# twitter-magnet.net
KiCad netlist of a schematic drawn in EAGLE
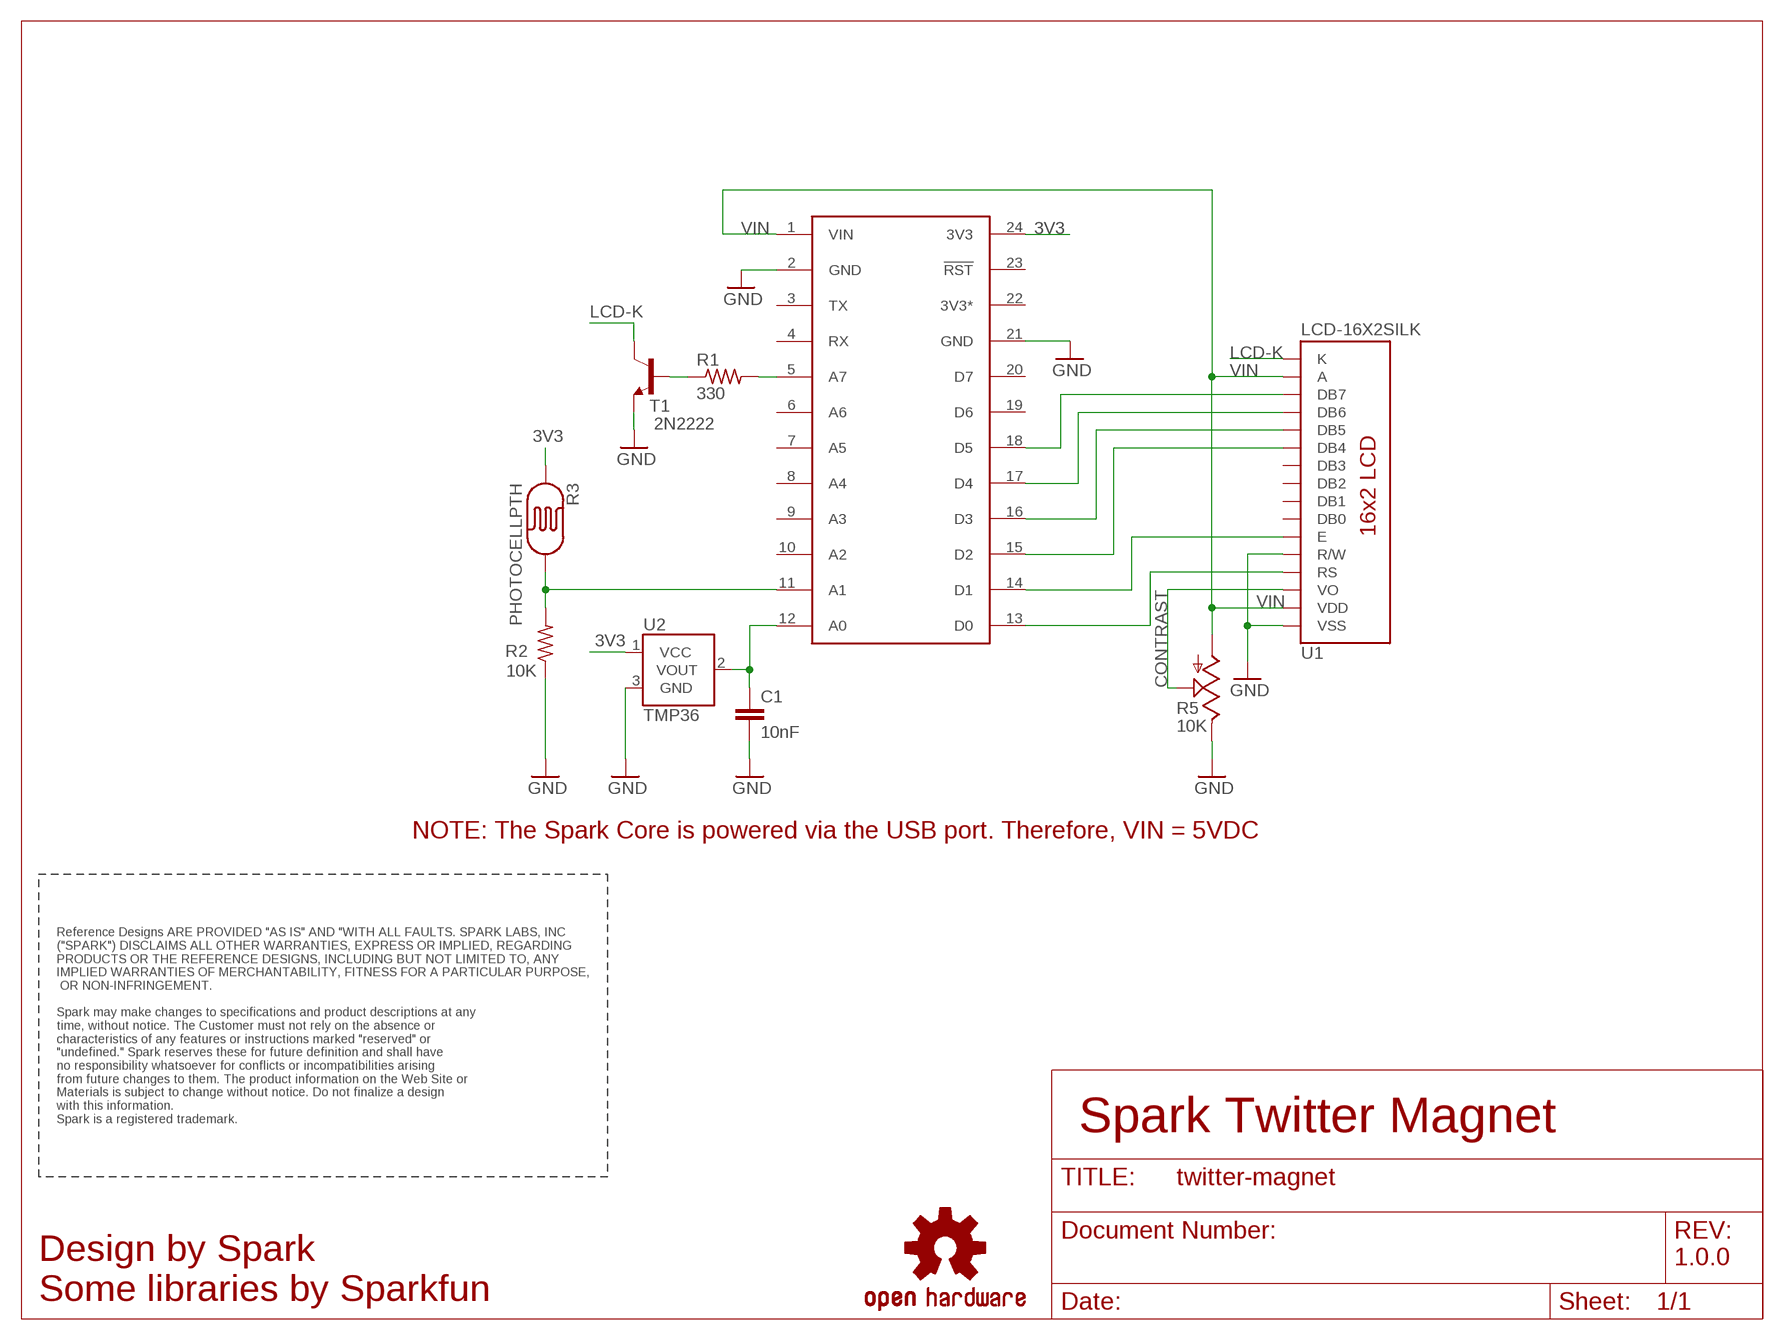
[diagram p0: schematic, sheet 1]

(export (version "E")
  (design (tool "Eeschema 10.0.6"))
  (components
    (comp (ref "C1")
      (value "10nF")
      (footprint "eagle-import:CAP-PTH-SMALLEZ")
      (libsource (lib "eagle-import") (part "CAPEZ"))
    )
    (comp (ref "LOGO1")
      (value "OSHW-LOGOM")
      (footprint "eagle-import:OSHW-LOGO-M")
      (libsource (lib "eagle-import") (part "OSHW-LOGOM"))
    )
    (comp (ref "R1")
      (value "330")
      (footprint "eagle-import:0207_10")
      (libsource (lib "eagle-import") (part "R-US_0207/10"))
    )
    (comp (ref "R2")
      (value "10K")
      (footprint "eagle-import:0207_10")
      (libsource (lib "eagle-import") (part "R-US_0207/10"))
    )
    (comp (ref "R3")
      (value "PHOTOCELLPTH")
      (footprint "eagle-import:PHOTOCELL")
      (libsource (lib "eagle-import") (part "PHOTOCELLPTH"))
    )
    (comp (ref "R5")
      (value "10K")
      (footprint "eagle-import:B25X")
      (libsource (lib "eagle-import") (part "TRIM_US-B25X"))
    )
    (comp (ref "T1")
      (value "2N2222")
      (footprint "eagle-import:TO92-EBC")
      (libsource (lib "eagle-import") (part "-NPN-TO92-EBC"))
    )
    (comp (ref "U$1")
      (value "SPARK_CORECORE")
      (footprint "eagle-import:SPARK_CORE")
      (libsource (lib "eagle-import") (part "SPARK_CORECORE"))
    )
    (comp (ref "U1")
      (value "LCD-16X2SILK")
      (footprint "eagle-import:LCD-16X2")
      (libsource (lib "eagle-import") (part "LCD-16X2SILK"))
    )
    (comp (ref "U2")
      (value "TMP36")
      (footprint "eagle-import:TO-92-KIT")
      (libsource (lib "eagle-import") (part "TMP36TO-92-KIT"))
    )
  )
  (nets
    (net (code "1") (name "/3V3") (class "Default")
      (node (ref "R3") (pin "1") (pinfunction "P$1_1") (pintype "bidirectional"))
      (node (ref "U$1") (pin "24") (pinfunction "3V3_24") (pintype "power_in"))
      (node (ref "U2") (pin "1") (pinfunction "VCC_1") (pintype "bidirectional"))
    )
    (net (code "2") (name "/3V3*") (class "Default")
      (node (ref "U$1") (pin "22") (pinfunction "3V3*_22") (pintype "power_in"))
    )
    (net (code "3") (name "/CONTRAST") (class "Default")
      (node (ref "R5") (pin "S") (pinfunction "S_S") (pintype "passive"))
      (node (ref "U1") (pin "3") (pinfunction "VO_3") (pintype "bidirectional"))
    )
    (net (code "4") (name "/LCD-K") (class "Default")
      (node (ref "T1") (pin "C") (pinfunction "C_C") (pintype "passive"))
      (node (ref "U1") (pin "16") (pinfunction "K_16") (pintype "power_in"))
    )
    (net (code "5") (name "/VIN") (class "Default")
      (node (ref "R5") (pin "A") (pinfunction "A_A") (pintype "passive"))
      (node (ref "U$1") (pin "1") (pinfunction "VIN_1") (pintype "power_in"))
      (node (ref "U1") (pin "15") (pinfunction "A_15") (pintype "power_in"))
      (node (ref "U1") (pin "2") (pinfunction "VDD_2") (pintype "power_in"))
    )
    (net (code "6") (name "GND") (class "Default")
      (node (ref "C1") (pin "2") (pinfunction "2_2") (pintype "passive"))
      (node (ref "R2") (pin "1") (pinfunction "1_1") (pintype "passive"))
      (node (ref "R5") (pin "E") (pinfunction "E_E") (pintype "passive"))
      (node (ref "T1") (pin "E") (pinfunction "E_E") (pintype "passive"))
      (node (ref "U$1") (pin "2") (pinfunction "GND_2") (pintype "power_in"))
      (node (ref "U$1") (pin "21") (pinfunction "GND_21") (pintype "power_in"))
      (node (ref "U1") (pin "1") (pinfunction "VSS_1") (pintype "power_in"))
      (node (ref "U1") (pin "5") (pinfunction "R/W_5") (pintype "input"))
      (node (ref "U2") (pin "3") (pinfunction "GND_3") (pintype "bidirectional"))
    )
    (net (code "7") (name "Net-(R1-Pad1)") (class "Default")
      (node (ref "R1") (pin "1") (pinfunction "1_1") (pintype "passive"))
      (node (ref "T1") (pin "B") (pinfunction "B_B") (pintype "passive"))
    )
    (net (code "8") (name "Net-(R3-P$2)") (class "Default")
      (node (ref "R2") (pin "2") (pinfunction "2_2") (pintype "passive"))
      (node (ref "R3") (pin "2") (pinfunction "P$2_2") (pintype "bidirectional"))
      (node (ref "U$1") (pin "11") (pinfunction "A1_11") (pintype "bidirectional"))
    )
    (net (code "9") (name "Net-(U$1-A0)") (class "Default")
      (node (ref "C1") (pin "1") (pinfunction "1_1") (pintype "passive"))
      (node (ref "U$1") (pin "12") (pinfunction "A0_12") (pintype "bidirectional"))
      (node (ref "U2") (pin "2") (pinfunction "VOUT_2") (pintype "bidirectional"))
    )
    (net (code "10") (name "Net-(U$1-A7)") (class "Default")
      (node (ref "R1") (pin "2") (pinfunction "2_2") (pintype "passive"))
      (node (ref "U$1") (pin "5") (pinfunction "A7_5") (pintype "bidirectional"))
    )
    (net (code "11") (name "Net-(U$1-D0)") (class "Default")
      (node (ref "U$1") (pin "13") (pinfunction "D0_13") (pintype "bidirectional"))
      (node (ref "U1") (pin "4") (pinfunction "RS_4") (pintype "input"))
    )
    (net (code "12") (name "Net-(U$1-D1)") (class "Default")
      (node (ref "U$1") (pin "14") (pinfunction "D1_14") (pintype "bidirectional"))
      (node (ref "U1") (pin "6") (pinfunction "E_6") (pintype "input"))
    )
    (net (code "13") (name "Net-(U$1-D2)") (class "Default")
      (node (ref "U$1") (pin "15") (pinfunction "D2_15") (pintype "bidirectional"))
      (node (ref "U1") (pin "11") (pinfunction "DB4_11") (pintype "bidirectional"))
    )
    (net (code "14") (name "Net-(U$1-D3)") (class "Default")
      (node (ref "U$1") (pin "16") (pinfunction "D3_16") (pintype "bidirectional"))
      (node (ref "U1") (pin "12") (pinfunction "DB5_12") (pintype "bidirectional"))
    )
    (net (code "15") (name "Net-(U$1-D4)") (class "Default")
      (node (ref "U$1") (pin "17") (pinfunction "D4_17") (pintype "bidirectional"))
      (node (ref "U1") (pin "13") (pinfunction "DB6_13") (pintype "bidirectional"))
    )
    (net (code "16") (name "Net-(U$1-D5)") (class "Default")
      (node (ref "U$1") (pin "18") (pinfunction "D5_18") (pintype "bidirectional"))
      (node (ref "U1") (pin "14") (pinfunction "DB7_14") (pintype "bidirectional"))
    )
    (net (code "17") (name "unconnected-(U$1-A2-Pad10)") (class "Default")
      (node (ref "U$1") (pin "10") (pinfunction "A2_10") (pintype "bidirectional"))
    )
    (net (code "18") (name "unconnected-(U$1-A3-Pad9)") (class "Default")
      (node (ref "U$1") (pin "9") (pinfunction "A3_9") (pintype "bidirectional"))
    )
    (net (code "19") (name "unconnected-(U$1-A4-Pad8)") (class "Default")
      (node (ref "U$1") (pin "8") (pinfunction "A4_8") (pintype "bidirectional"))
    )
    (net (code "20") (name "unconnected-(U$1-A5-Pad7)") (class "Default")
      (node (ref "U$1") (pin "7") (pinfunction "A5_7") (pintype "bidirectional"))
    )
    (net (code "21") (name "unconnected-(U$1-A6-Pad6)") (class "Default")
      (node (ref "U$1") (pin "6") (pinfunction "A6_6") (pintype "bidirectional"))
    )
    (net (code "22") (name "unconnected-(U$1-D6-Pad19)") (class "Default")
      (node (ref "U$1") (pin "19") (pinfunction "D6_19") (pintype "bidirectional"))
    )
    (net (code "23") (name "unconnected-(U$1-D7-Pad20)") (class "Default")
      (node (ref "U$1") (pin "20") (pinfunction "D7_20") (pintype "bidirectional"))
    )
    (net (code "24") (name "unconnected-(U$1-RX-Pad4)") (class "Default")
      (node (ref "U$1") (pin "4") (pinfunction "RX_4") (pintype "bidirectional"))
    )
    (net (code "25") (name "unconnected-(U$1-TX-Pad3)") (class "Default")
      (node (ref "U$1") (pin "3") (pinfunction "TX_3") (pintype "bidirectional"))
    )
    (net (code "26") (name "unconnected-(U$1-~{RST}-Pad23)") (class "Default")
      (node (ref "U$1") (pin "23") (pinfunction "~{RST}_23") (pintype "bidirectional"))
    )
    (net (code "27") (name "unconnected-(U1-DB0-Pad7)") (class "Default")
      (node (ref "U1") (pin "7") (pinfunction "DB0_7") (pintype "bidirectional"))
    )
    (net (code "28") (name "unconnected-(U1-DB1-Pad8)") (class "Default")
      (node (ref "U1") (pin "8") (pinfunction "DB1_8") (pintype "bidirectional"))
    )
    (net (code "29") (name "unconnected-(U1-DB2-Pad9)") (class "Default")
      (node (ref "U1") (pin "9") (pinfunction "DB2_9") (pintype "bidirectional"))
    )
    (net (code "30") (name "unconnected-(U1-DB3-Pad10)") (class "Default")
      (node (ref "U1") (pin "10") (pinfunction "DB3_10") (pintype "bidirectional"))
    )
  )
)
